# fpga-tx2.net
KiCad netlist of a schematic drawn in Altium Designer
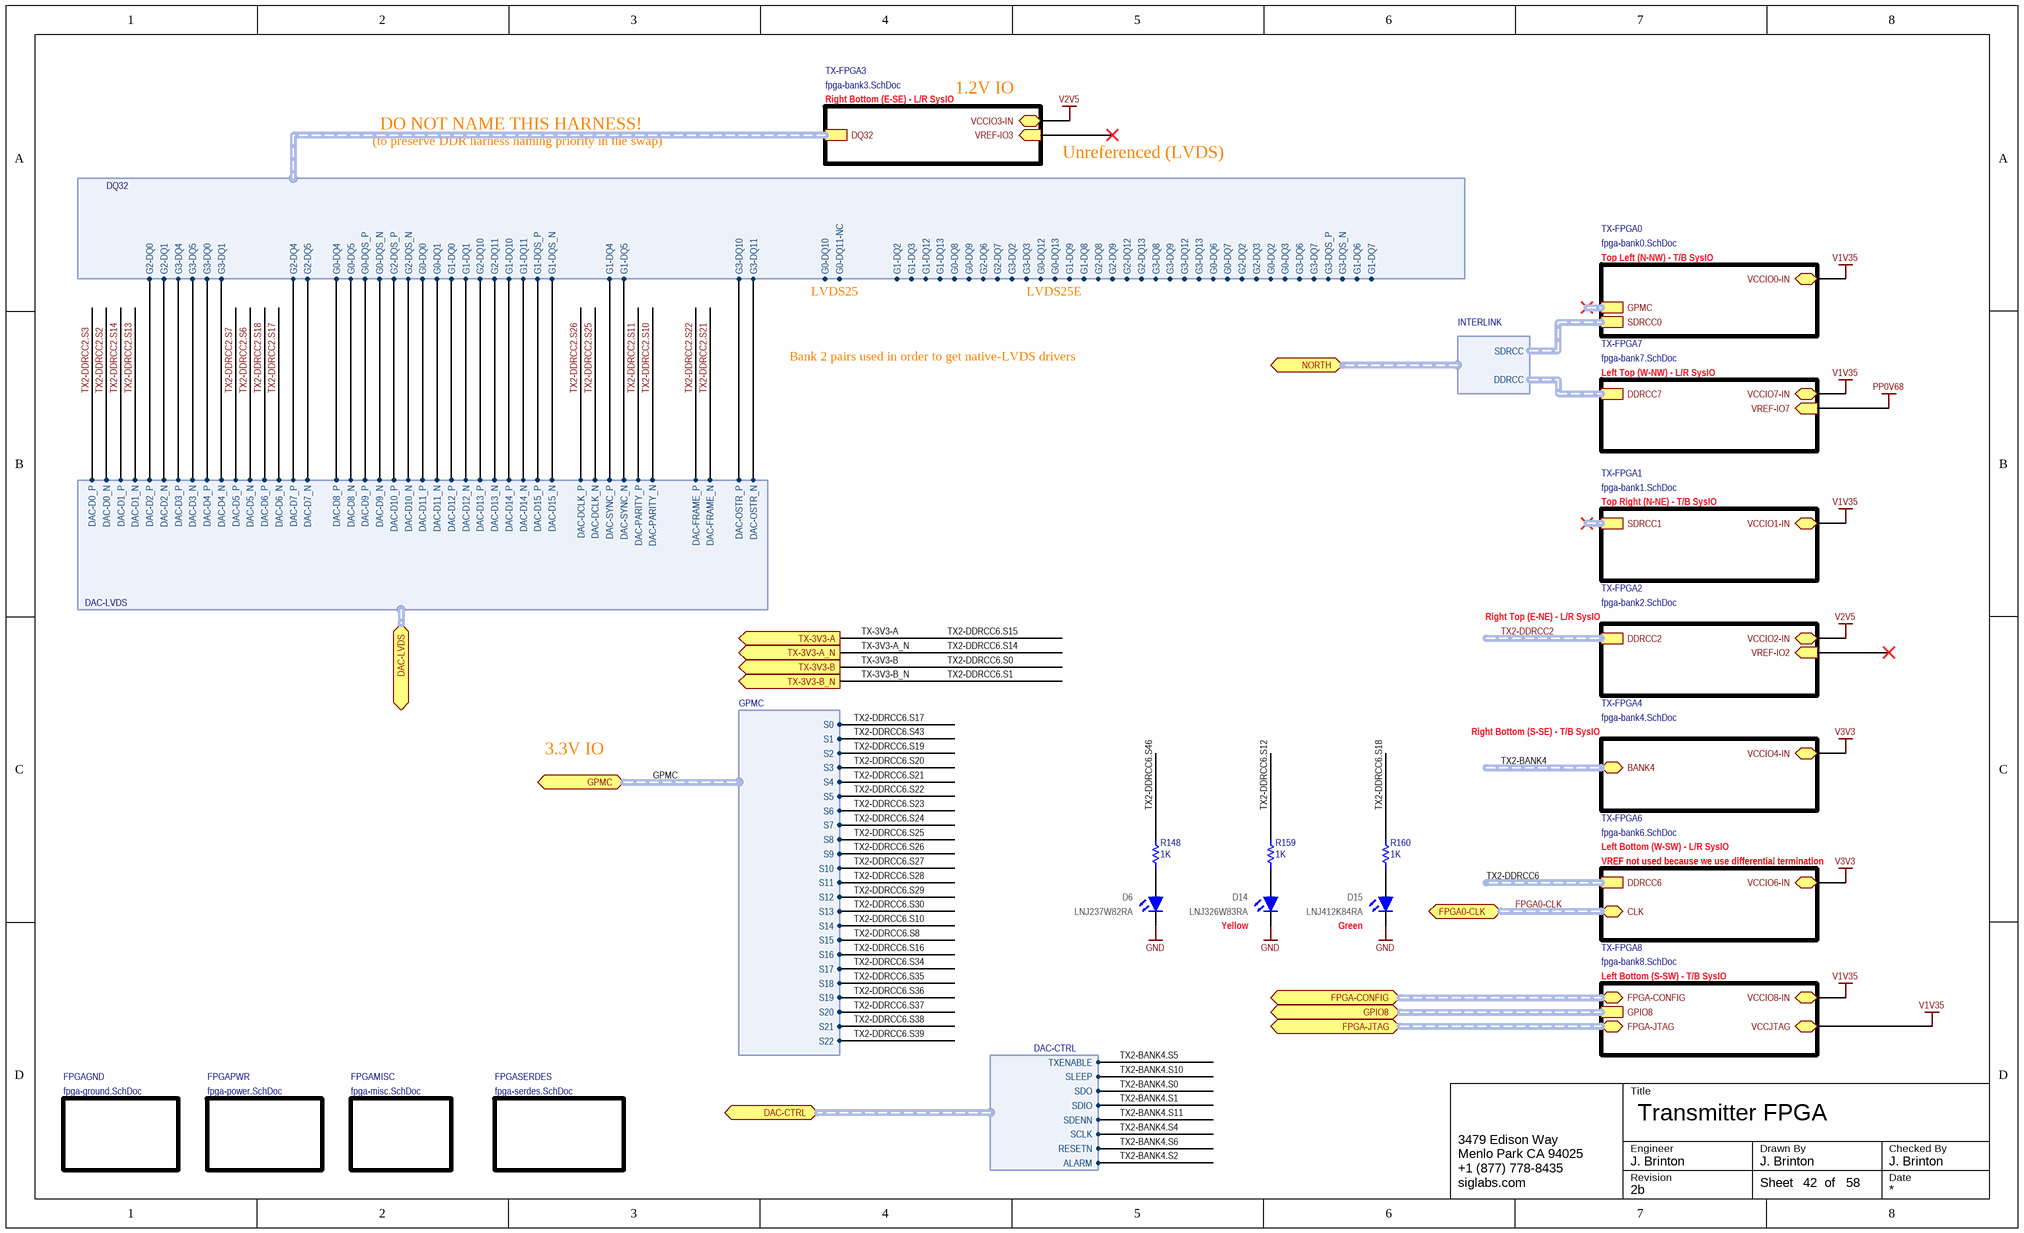
[diagram p0: fpga-tx2.SchDoc]

(export (version "E")
  (design (tool "Eeschema 10.0.6"))
  (components
    (comp (ref "D6")
      (value "LNJ237W82RA")
      (footprint "0603_LED")
      (description "LED, SMT 0603, Color Red, 5mA, 1.85V")
      (fields (field (name "MANUFACTURER") "Panasonic"))
      (libsource (lib "generic") (part "LED0603RD"))
    )
    (comp (ref "D14")
      (value "LNJ326W83RA")
      (footprint "0603_LED")
      (description "LED, SMT 0603, Color Green, 10mA, 2.05V")
      (fields (field (name "MANUFACTURER") "Panasonic"))
      (libsource (lib "generic") (part "LED0603GR"))
    )
    (comp (ref "D15")
      (value "LNJ412K84RA")
      (footprint "0603_LED")
      (description "LED, SMT 0603, Color Yellow, 10mA, 2.05V")
      (fields (field (name "MANUFACTURER") "Panasonic"))
      (libsource (lib "generic") (part "LED0603Y"))
    )
    (comp (ref "R148")
      (value "1K")
      (footprint "generic:0402")
      (description "Thick Film Resistor 1k ±1% 0402")
      (fields (field (name "MANUFACTURER") "Yageo") (field (name "TOLERANCE") "±1%"))
      (libsource (lib "Graviton") (part "RES 0402"))
    )
    (comp (ref "R159")
      (value "1K")
      (footprint "generic:0402")
      (description "Thick Film Resistor 1k ±1% 0402")
      (fields (field (name "MANUFACTURER") "Yageo") (field (name "TOLERANCE") "±1%"))
      (libsource (lib "Graviton") (part "RES 0402"))
    )
    (comp (ref "R160")
      (value "1K")
      (footprint "generic:0402")
      (description "Thick Film Resistor 1k ±1% 0402")
      (fields (field (name "MANUFACTURER") "Yageo") (field (name "TOLERANCE") "±1%"))
      (libsource (lib "Graviton") (part "RES 0402"))
    )
  )
  (nets
    (net (code "50") (name "/TX2-DDRCC6.S12") (class "Default")
      (node (ref "R159") (pin "2") (pinfunction "2_2") (pintype "passive"))
    )
    (net (code "53") (name "/TX2-DDRCC6.S18") (class "Default")
      (node (ref "R160") (pin "2") (pinfunction "2_2") (pintype "passive"))
    )
    (net (code "73") (name "/TX2-DDRCC6.S46") (class "Default")
      (node (ref "R148") (pin "2") (pinfunction "2_2") (pintype "passive"))
    )
    (net (code "84") (name "GND") (class "Default")
      (node (ref "D14") (pin "2") (pinfunction "K_2") (pintype "passive"))
      (node (ref "D15") (pin "2") (pinfunction "K_2") (pintype "passive"))
      (node (ref "D6") (pin "2") (pinfunction "K_2") (pintype "passive"))
    )
    (net (code "85") (name "Net-(D6-A)") (class "Default")
      (node (ref "D6") (pin "1") (pinfunction "A_1") (pintype "passive"))
      (node (ref "R148") (pin "1") (pinfunction "1_1") (pintype "passive"))
    )
    (net (code "86") (name "Net-(D14-A)") (class "Default")
      (node (ref "D14") (pin "1") (pinfunction "A_1") (pintype "passive"))
      (node (ref "R159") (pin "1") (pinfunction "1_1") (pintype "passive"))
    )
    (net (code "87") (name "Net-(D15-A)") (class "Default")
      (node (ref "D15") (pin "1") (pinfunction "A_1") (pintype "passive"))
      (node (ref "R160") (pin "1") (pinfunction "1_1") (pintype "passive"))
    )
  )
)
